# Zusatzprint_Raspberry_Pi_Zero.net
KiCad netlist of a schematic drawn in EAGLE
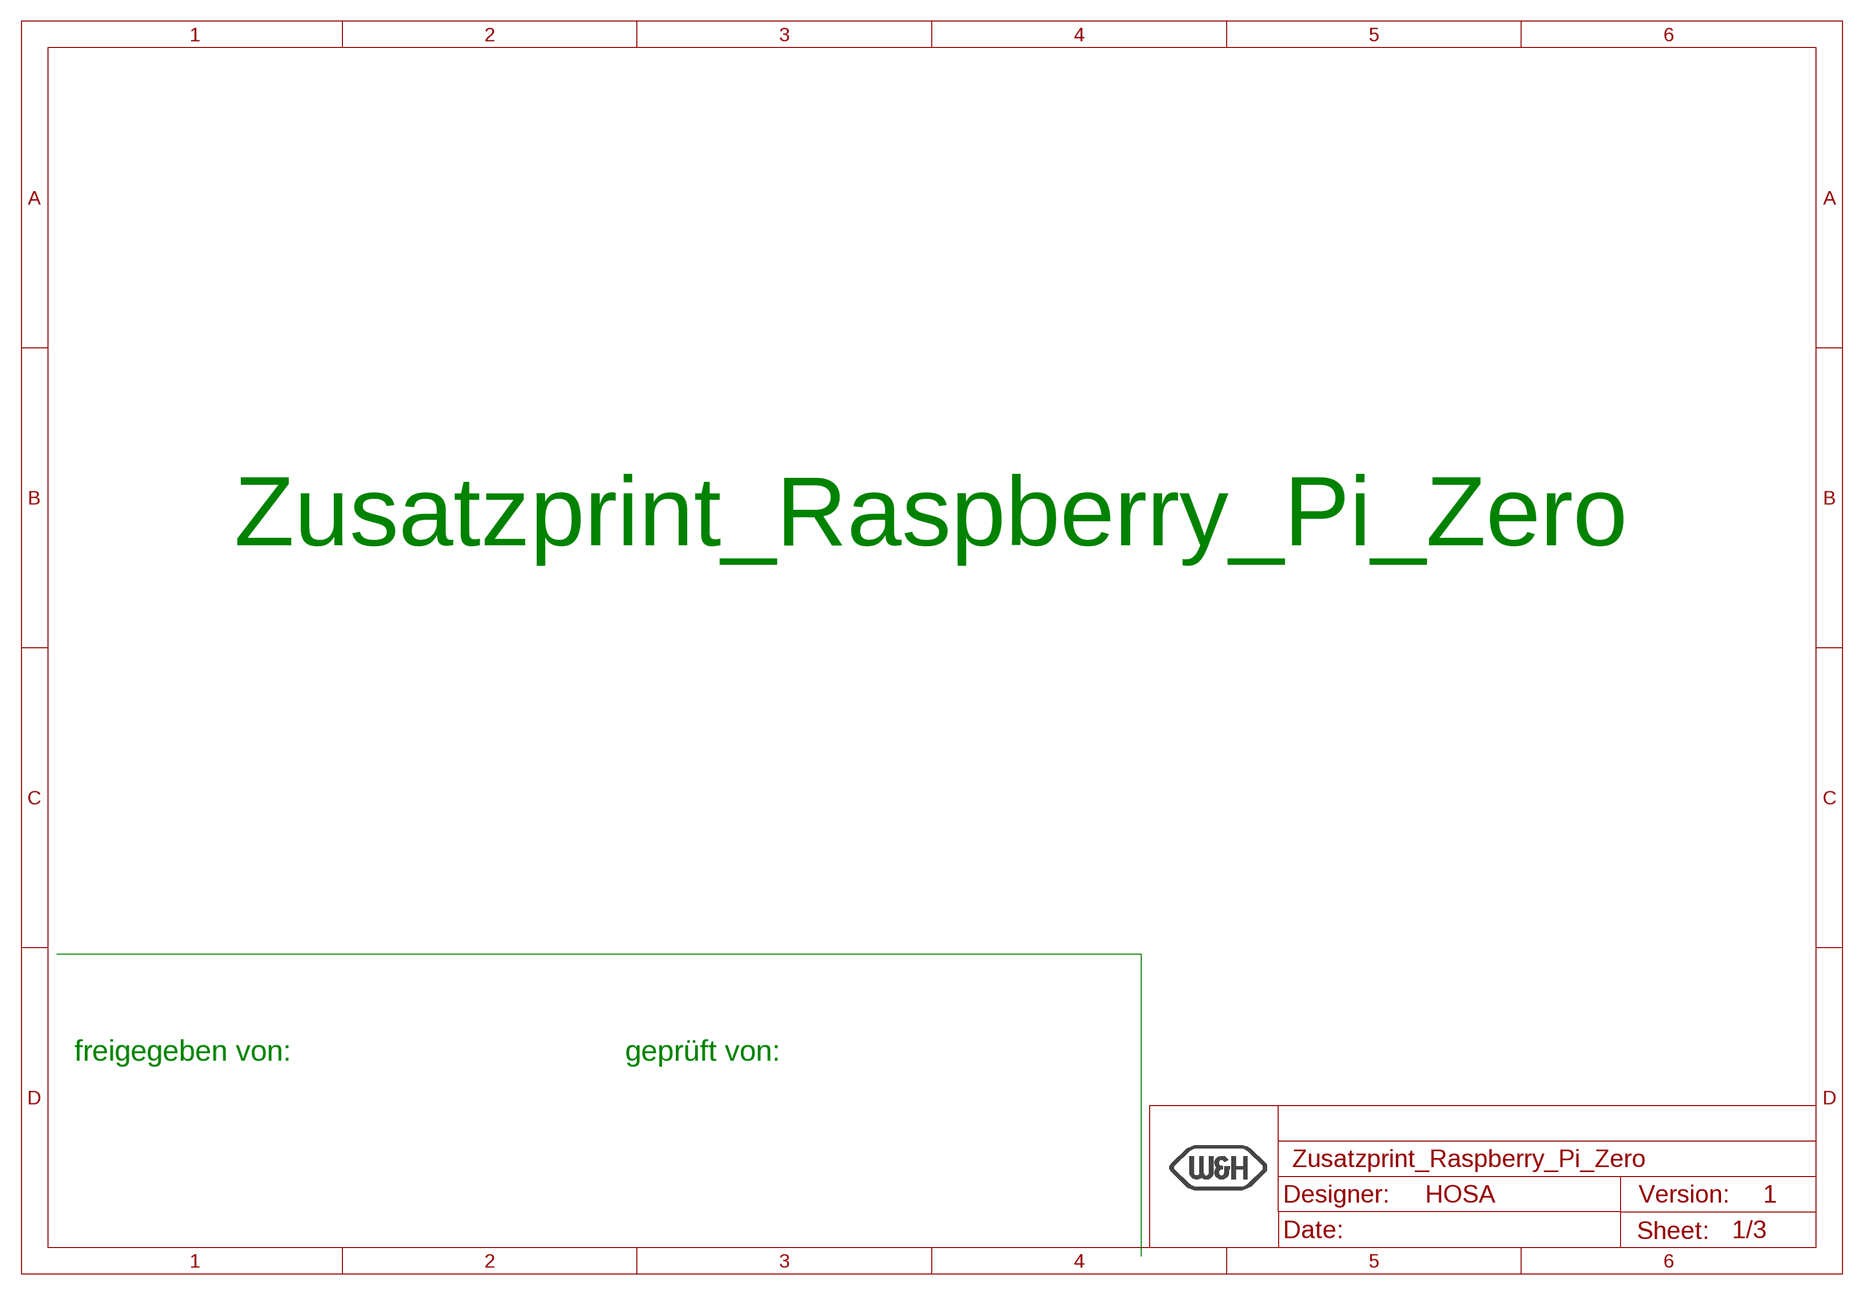
[diagram p0: schematic, sheet 1]
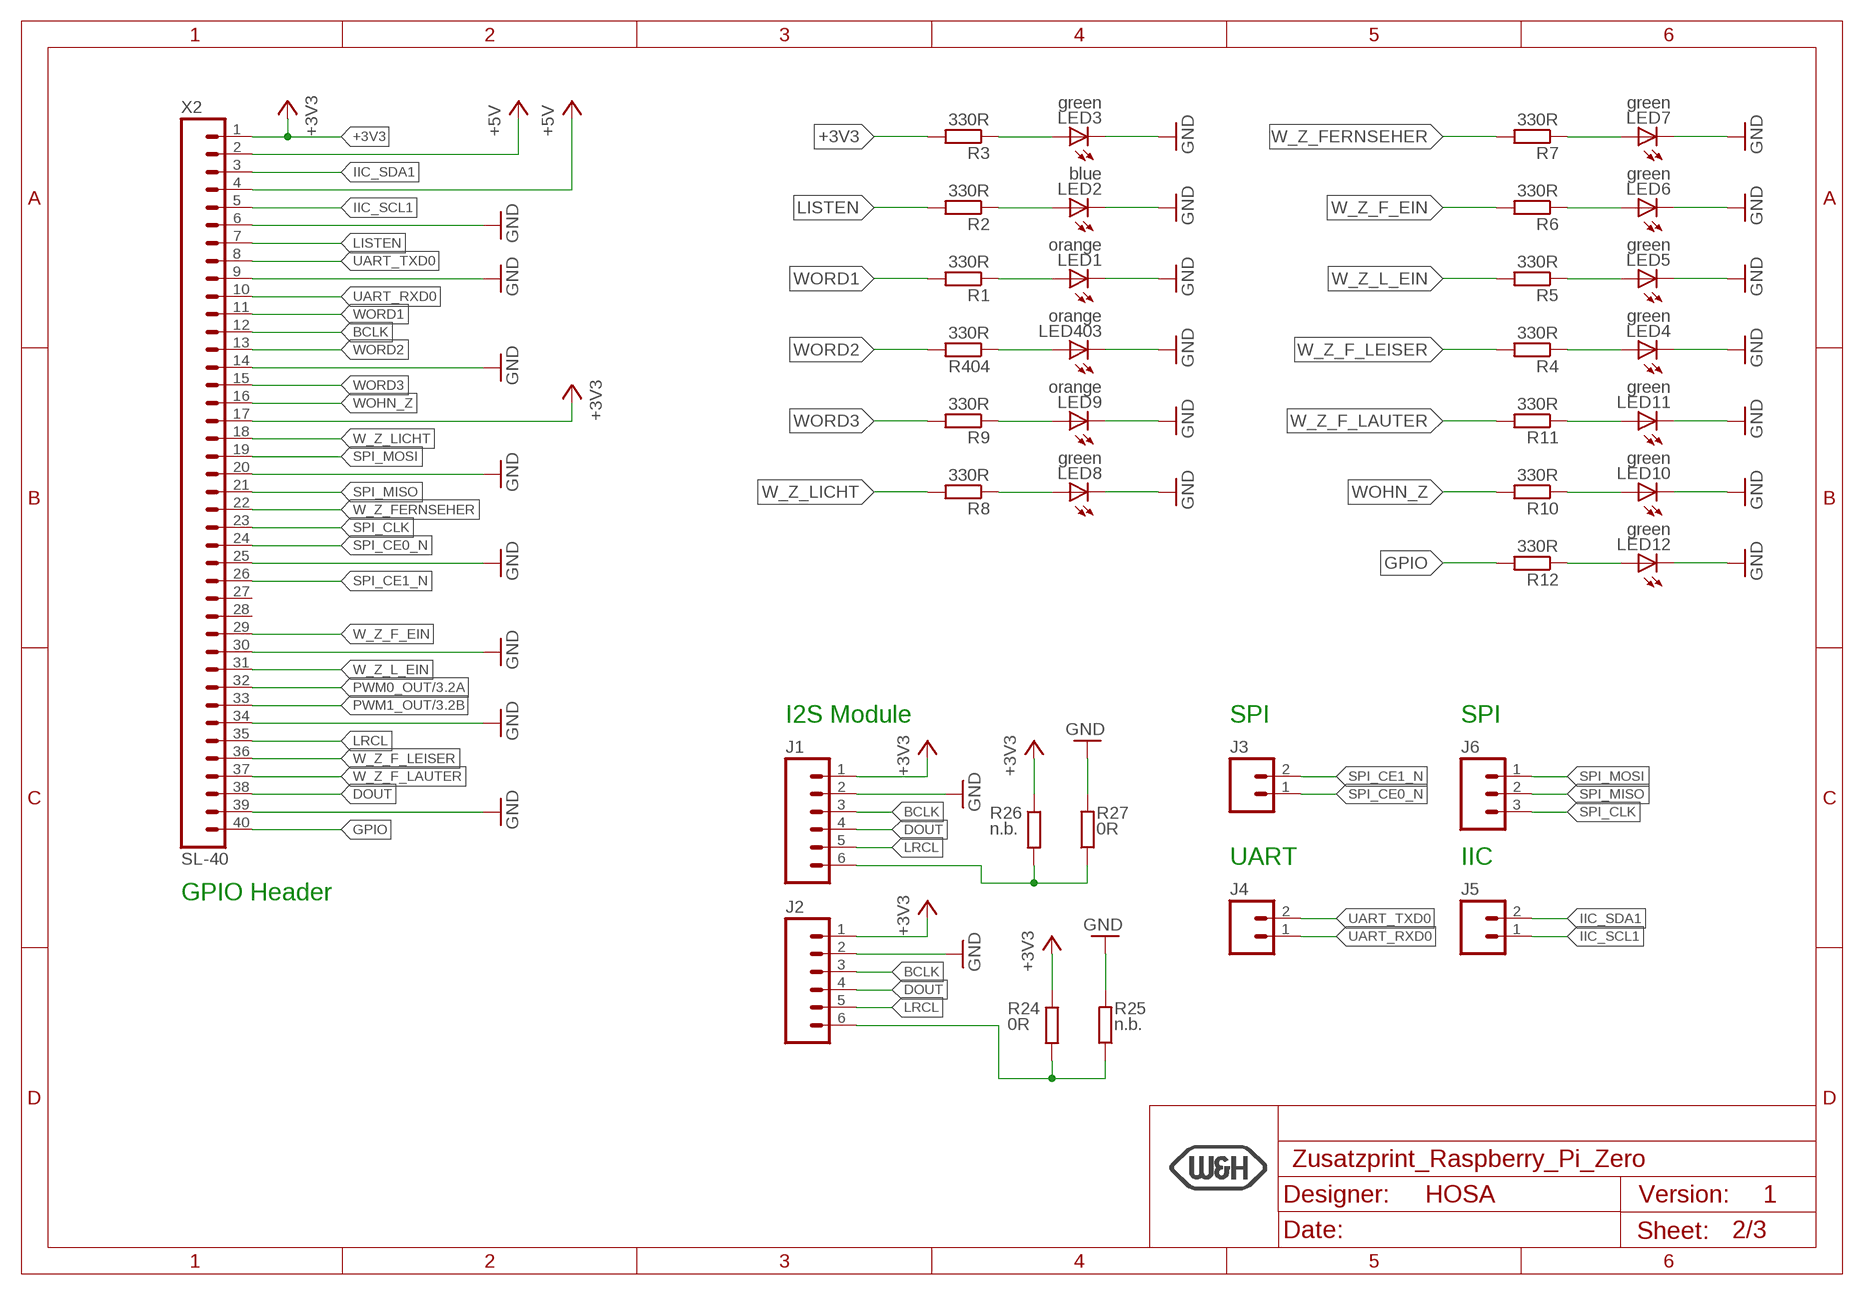
[diagram p1: schematic, sheet 2]
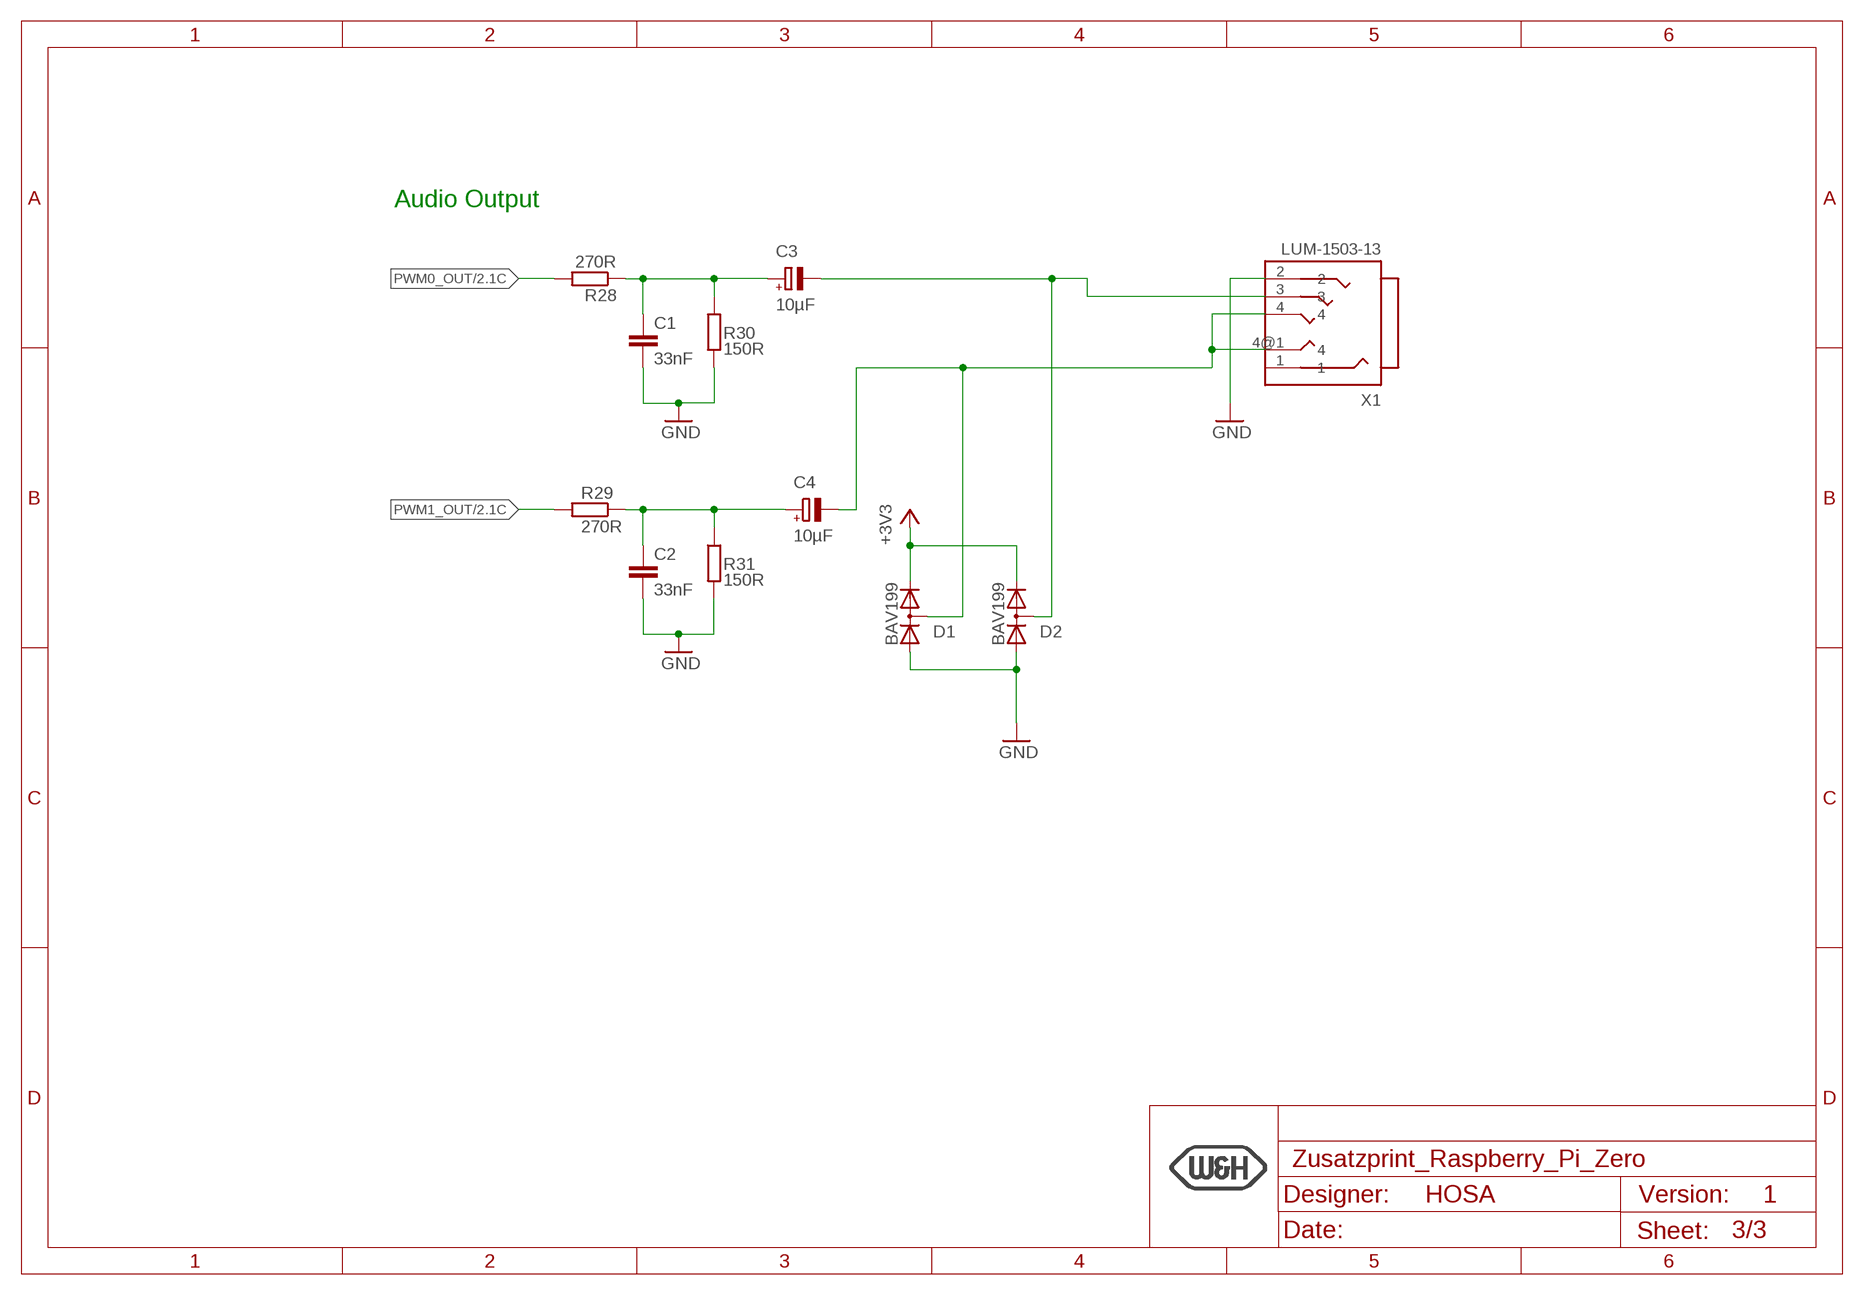
[diagram p2: schematic, sheet 3]

(export (version "E")
  (design (tool "Eeschema 10.0.6"))
  (components
    (comp (ref "J1")
      (value "S-LEISTE-06")
      (footprint "eagle-import:BL-06")
      (libsource (lib "eagle-import") (part "-LEISTE-06S"))
    )
    (comp (ref "J2")
      (value "S-LEISTE-06")
      (footprint "eagle-import:BL-06")
      (libsource (lib "eagle-import") (part "-LEISTE-06S"))
    )
    (comp (ref "J3")
      (value "S-LEISTE-02")
      (footprint "eagle-import:BL-02")
      (libsource (lib "eagle-import") (part "-LEISTE-02S"))
    )
    (comp (ref "J4")
      (value "S-LEISTE-02")
      (footprint "eagle-import:BL-02")
      (libsource (lib "eagle-import") (part "-LEISTE-02S"))
    )
    (comp (ref "J5")
      (value "S-LEISTE-02")
      (footprint "eagle-import:BL-02")
      (libsource (lib "eagle-import") (part "-LEISTE-02S"))
    )
    (comp (ref "J6")
      (value "S-LEISTE-03")
      (footprint "eagle-import:BL-03")
      (libsource (lib "eagle-import") (part "-LEISTE-03S"))
    )
    (comp (ref "LED1")
      (value "orange")
      (footprint "eagle-import:CHIP-LED0805")
      (libsource (lib "eagle-import") (part "LEDCHIP-LED0805"))
    )
    (comp (ref "LED2")
      (value "blue")
      (footprint "eagle-import:CHIP-LED0805")
      (libsource (lib "eagle-import") (part "LEDCHIP-LED0805"))
    )
    (comp (ref "LED3")
      (value "green")
      (footprint "eagle-import:CHIP-LED0805")
      (libsource (lib "eagle-import") (part "LEDCHIP-LED0805"))
    )
    (comp (ref "LED4")
      (value "green")
      (footprint "eagle-import:CHIP-LED0805")
      (libsource (lib "eagle-import") (part "LEDCHIP-LED0805"))
    )
    (comp (ref "LED5")
      (value "green")
      (footprint "eagle-import:CHIP-LED0805")
      (libsource (lib "eagle-import") (part "LEDCHIP-LED0805"))
    )
    (comp (ref "LED6")
      (value "green")
      (footprint "eagle-import:CHIP-LED0805")
      (libsource (lib "eagle-import") (part "LEDCHIP-LED0805"))
    )
    (comp (ref "LED7")
      (value "green")
      (footprint "eagle-import:CHIP-LED0805")
      (libsource (lib "eagle-import") (part "LEDCHIP-LED0805"))
    )
    (comp (ref "LED8")
      (value "green")
      (footprint "eagle-import:CHIP-LED0805")
      (libsource (lib "eagle-import") (part "LEDCHIP-LED0805"))
    )
    (comp (ref "LED9")
      (value "orange")
      (footprint "eagle-import:CHIP-LED0805")
      (libsource (lib "eagle-import") (part "LEDCHIP-LED0805"))
    )
    (comp (ref "LED10")
      (value "green")
      (footprint "eagle-import:CHIP-LED0805")
      (libsource (lib "eagle-import") (part "LEDCHIP-LED0805"))
    )
    (comp (ref "LED11")
      (value "green")
      (footprint "eagle-import:CHIP-LED0805")
      (libsource (lib "eagle-import") (part "LEDCHIP-LED0805"))
    )
    (comp (ref "LED12")
      (value "green")
      (footprint "eagle-import:CHIP-LED0805")
      (libsource (lib "eagle-import") (part "LEDCHIP-LED0805"))
    )
    (comp (ref "LED403")
      (value "orange")
      (footprint "eagle-import:CHIP-LED0805")
      (libsource (lib "eagle-import") (part "LEDCHIP-LED0805"))
    )
    (comp (ref "R1")
      (value "330R")
      (footprint "eagle-import:M0805")
      (libsource (lib "eagle-import") (part "R-EU_M0805"))
    )
    (comp (ref "R2")
      (value "330R")
      (footprint "eagle-import:M0805")
      (libsource (lib "eagle-import") (part "R-EU_M0805"))
    )
    (comp (ref "R3")
      (value "330R")
      (footprint "eagle-import:M0805")
      (libsource (lib "eagle-import") (part "R-EU_M0805"))
    )
    (comp (ref "R4")
      (value "330R")
      (footprint "eagle-import:M0805")
      (libsource (lib "eagle-import") (part "R-EU_M0805"))
    )
    (comp (ref "R5")
      (value "330R")
      (footprint "eagle-import:M0805")
      (libsource (lib "eagle-import") (part "R-EU_M0805"))
    )
    (comp (ref "R6")
      (value "330R")
      (footprint "eagle-import:M0805")
      (libsource (lib "eagle-import") (part "R-EU_M0805"))
    )
    (comp (ref "R7")
      (value "330R")
      (footprint "eagle-import:M0805")
      (libsource (lib "eagle-import") (part "R-EU_M0805"))
    )
    (comp (ref "R8")
      (value "330R")
      (footprint "eagle-import:M0805")
      (libsource (lib "eagle-import") (part "R-EU_M0805"))
    )
    (comp (ref "R9")
      (value "330R")
      (footprint "eagle-import:M0805")
      (libsource (lib "eagle-import") (part "R-EU_M0805"))
    )
    (comp (ref "R10")
      (value "330R")
      (footprint "eagle-import:M0805")
      (libsource (lib "eagle-import") (part "R-EU_M0805"))
    )
    (comp (ref "R11")
      (value "330R")
      (footprint "eagle-import:M0805")
      (libsource (lib "eagle-import") (part "R-EU_M0805"))
    )
    (comp (ref "R12")
      (value "330R")
      (footprint "eagle-import:M0805")
      (libsource (lib "eagle-import") (part "R-EU_M0805"))
    )
    (comp (ref "R24")
      (value "0R")
      (footprint "eagle-import:M0805")
      (libsource (lib "eagle-import") (part "R-EU_M0805"))
    )
    (comp (ref "R25")
      (value "n.b.")
      (footprint "eagle-import:M0805")
      (libsource (lib "eagle-import") (part "R-EU_M0805"))
    )
    (comp (ref "R26")
      (value "n.b.")
      (footprint "eagle-import:M0805")
      (libsource (lib "eagle-import") (part "R-EU_M0805"))
    )
    (comp (ref "R27")
      (value "0R")
      (footprint "eagle-import:M0805")
      (libsource (lib "eagle-import") (part "R-EU_M0805"))
    )
    (comp (ref "R404")
      (value "330R")
      (footprint "eagle-import:M0805")
      (libsource (lib "eagle-import") (part "R-EU_M0805"))
    )
    (comp (ref "X2")
      (value "SL-40")
      (footprint "eagle-import:SL_40")
      (libsource (lib "eagle-import") (part "SL-40"))
    )
    (comp (ref "C1")
      (value "33nF")
      (footprint "eagle-import:C0805")
      (libsource (lib "eagle-import") (part "C-EUC0805"))
    )
    (comp (ref "C2")
      (value "33nF")
      (footprint "eagle-import:C0805")
      (libsource (lib "eagle-import") (part "C-EUC0805"))
    )
    (comp (ref "C3")
      (value "10µF")
      (footprint "eagle-import:E2,5-6")
      (libsource (lib "eagle-import") (part "CPOL-EUE2.5-6"))
    )
    (comp (ref "C4")
      (value "10µF")
      (footprint "eagle-import:E2,5-6")
      (libsource (lib "eagle-import") (part "CPOL-EUE2.5-6"))
    )
    (comp (ref "D1")
      (value "BAV199")
      (footprint "eagle-import:SOT23")
      (libsource (lib "eagle-import") (part "BAV199"))
    )
    (comp (ref "D2")
      (value "BAV199")
      (footprint "eagle-import:SOT23")
      (libsource (lib "eagle-import") (part "BAV199"))
    )
    (comp (ref "R28")
      (value "270R")
      (footprint "eagle-import:M0805")
      (libsource (lib "eagle-import") (part "R-EU_M0805"))
    )
    (comp (ref "R29")
      (value "270R")
      (footprint "eagle-import:M0805")
      (libsource (lib "eagle-import") (part "R-EU_M0805"))
    )
    (comp (ref "R30")
      (value "150R")
      (footprint "eagle-import:M0805")
      (libsource (lib "eagle-import") (part "R-EU_M0805"))
    )
    (comp (ref "R31")
      (value "150R")
      (footprint "eagle-import:M0805")
      (libsource (lib "eagle-import") (part "R-EU_M0805"))
    )
    (comp (ref "X1")
      (value "LUM-1503-13")
      (footprint "eagle-import:1503-13")
      (fields (field (name "MF") "Lumberg") (field (name "MPN") "1503 13"))
      (libsource (lib "eagle-import") (part "LUM-1503-13"))
    )
  )
  (nets
    (net (code "1") (name "+3V3") (class "Default")
      (node (ref "D1") (pin "2") (pinfunction "C_2") (pintype "passive"))
      (node (ref "D2") (pin "2") (pinfunction "C_2") (pintype "passive"))
      (node (ref "J1") (pin "1") (pinfunction "1_1") (pintype "passive"))
      (node (ref "J2") (pin "1") (pinfunction "1_1") (pintype "passive"))
      (node (ref "R24") (pin "1") (pinfunction "1_1") (pintype "passive"))
      (node (ref "R26") (pin "1") (pinfunction "1_1") (pintype "passive"))
      (node (ref "R3") (pin "2") (pinfunction "2_2") (pintype "passive"))
      (node (ref "X2") (pin "1") (pinfunction "1_1") (pintype "passive"))
      (node (ref "X2") (pin "17") (pinfunction "17_17") (pintype "passive"))
    )
    (net (code "2") (name "+5V") (class "Default")
      (node (ref "X2") (pin "2") (pinfunction "2_2") (pintype "passive"))
      (node (ref "X2") (pin "4") (pinfunction "4_4") (pintype "passive"))
    )
    (net (code "3") (name "BCLK") (class "Default")
      (node (ref "J1") (pin "3") (pinfunction "3_3") (pintype "passive"))
      (node (ref "J2") (pin "3") (pinfunction "3_3") (pintype "passive"))
      (node (ref "X2") (pin "12") (pinfunction "12_12") (pintype "passive"))
    )
    (net (code "4") (name "DOUT") (class "Default")
      (node (ref "J1") (pin "4") (pinfunction "4_4") (pintype "passive"))
      (node (ref "J2") (pin "4") (pinfunction "4_4") (pintype "passive"))
      (node (ref "X2") (pin "38") (pinfunction "38_38") (pintype "passive"))
    )
    (net (code "5") (name "GND") (class "Default")
      (node (ref "C1") (pin "2") (pinfunction "2_2") (pintype "passive"))
      (node (ref "C2") (pin "2") (pinfunction "2_2") (pintype "passive"))
      (node (ref "D1") (pin "1") (pinfunction "A_1") (pintype "passive"))
      (node (ref "D2") (pin "1") (pinfunction "A_1") (pintype "passive"))
      (node (ref "J1") (pin "2") (pinfunction "2_2") (pintype "passive"))
      (node (ref "J2") (pin "2") (pinfunction "2_2") (pintype "passive"))
      (node (ref "LED1") (pin "C") (pinfunction "C_C") (pintype "passive"))
      (node (ref "LED10") (pin "C") (pinfunction "C_C") (pintype "passive"))
      (node (ref "LED11") (pin "C") (pinfunction "C_C") (pintype "passive"))
      (node (ref "LED12") (pin "C") (pinfunction "C_C") (pintype "passive"))
      (node (ref "LED2") (pin "C") (pinfunction "C_C") (pintype "passive"))
      (node (ref "LED3") (pin "C") (pinfunction "C_C") (pintype "passive"))
      (node (ref "LED4") (pin "C") (pinfunction "C_C") (pintype "passive"))
      (node (ref "LED403") (pin "C") (pinfunction "C_C") (pintype "passive"))
      (node (ref "LED5") (pin "C") (pinfunction "C_C") (pintype "passive"))
      (node (ref "LED6") (pin "C") (pinfunction "C_C") (pintype "passive"))
      (node (ref "LED7") (pin "C") (pinfunction "C_C") (pintype "passive"))
      (node (ref "LED8") (pin "C") (pinfunction "C_C") (pintype "passive"))
      (node (ref "LED9") (pin "C") (pinfunction "C_C") (pintype "passive"))
      (node (ref "R25") (pin "2") (pinfunction "2_2") (pintype "passive"))
      (node (ref "R27") (pin "2") (pinfunction "2_2") (pintype "passive"))
      (node (ref "R30") (pin "2") (pinfunction "2_2") (pintype "passive"))
      (node (ref "R31") (pin "2") (pinfunction "2_2") (pintype "passive"))
      (node (ref "X1") (pin "2") (pinfunction "2_2") (pintype "bidirectional"))
      (node (ref "X2") (pin "14") (pinfunction "14_14") (pintype "passive"))
      (node (ref "X2") (pin "20") (pinfunction "20_20") (pintype "passive"))
      (node (ref "X2") (pin "25") (pinfunction "25_25") (pintype "passive"))
      (node (ref "X2") (pin "30") (pinfunction "30_30") (pintype "passive"))
      (node (ref "X2") (pin "34") (pinfunction "34_34") (pintype "passive"))
      (node (ref "X2") (pin "39") (pinfunction "39_39") (pintype "passive"))
      (node (ref "X2") (pin "6") (pinfunction "6_6") (pintype "passive"))
      (node (ref "X2") (pin "9") (pinfunction "9_9") (pintype "passive"))
    )
    (net (code "6") (name "GPIO") (class "Default")
      (node (ref "R12") (pin "2") (pinfunction "2_2") (pintype "passive"))
      (node (ref "X2") (pin "40") (pinfunction "40_40") (pintype "passive"))
    )
    (net (code "7") (name "IIC_SCL1") (class "Default")
      (node (ref "J5") (pin "1") (pinfunction "1_1") (pintype "passive"))
      (node (ref "X2") (pin "5") (pinfunction "5_5") (pintype "passive"))
    )
    (net (code "8") (name "IIC_SDA1") (class "Default")
      (node (ref "J5") (pin "2") (pinfunction "2_2") (pintype "passive"))
      (node (ref "X2") (pin "3") (pinfunction "3_3") (pintype "passive"))
    )
    (net (code "9") (name "LISTEN") (class "Default")
      (node (ref "R2") (pin "2") (pinfunction "2_2") (pintype "passive"))
      (node (ref "X2") (pin "7") (pinfunction "7_7") (pintype "passive"))
    )
    (net (code "10") (name "LRCL") (class "Default")
      (node (ref "J1") (pin "5") (pinfunction "5_5") (pintype "passive"))
      (node (ref "J2") (pin "5") (pinfunction "5_5") (pintype "passive"))
      (node (ref "X2") (pin "35") (pinfunction "35_35") (pintype "passive"))
    )
    (net (code "11") (name "Net-(C1-Pad1)") (class "Default")
      (node (ref "C1") (pin "1") (pinfunction "1_1") (pintype "passive"))
      (node (ref "C3") (pin "+") (pinfunction "+_+") (pintype "passive"))
      (node (ref "R28") (pin "1") (pinfunction "1_1") (pintype "passive"))
      (node (ref "R30") (pin "1") (pinfunction "1_1") (pintype "passive"))
    )
    (net (code "12") (name "Net-(C2-Pad1)") (class "Default")
      (node (ref "C2") (pin "1") (pinfunction "1_1") (pintype "passive"))
      (node (ref "C4") (pin "+") (pinfunction "+_+") (pintype "passive"))
      (node (ref "R29") (pin "1") (pinfunction "1_1") (pintype "passive"))
      (node (ref "R31") (pin "1") (pinfunction "1_1") (pintype "passive"))
    )
    (net (code "13") (name "Net-(D1-AC)") (class "Default")
      (node (ref "C4") (pin "-") (pinfunction "-_-") (pintype "passive"))
      (node (ref "D1") (pin "3") (pinfunction "AC_3") (pintype "passive"))
      (node (ref "X1") (pin "4") (pinfunction "4_4") (pintype "bidirectional"))
      (node (ref "X1") (pin "4@1") (pinfunction "4_4@1") (pintype "bidirectional"))
    )
    (net (code "14") (name "Net-(D2-AC)") (class "Default")
      (node (ref "C3") (pin "-") (pinfunction "-_-") (pintype "passive"))
      (node (ref "D2") (pin "3") (pinfunction "AC_3") (pintype "passive"))
      (node (ref "X1") (pin "3") (pinfunction "3_3") (pintype "bidirectional"))
    )
    (net (code "15") (name "Net-(J1-Pad6)") (class "Default")
      (node (ref "J1") (pin "6") (pinfunction "6_6") (pintype "passive"))
      (node (ref "R26") (pin "2") (pinfunction "2_2") (pintype "passive"))
      (node (ref "R27") (pin "1") (pinfunction "1_1") (pintype "passive"))
    )
    (net (code "16") (name "Net-(J2-Pad6)") (class "Default")
      (node (ref "J2") (pin "6") (pinfunction "6_6") (pintype "passive"))
      (node (ref "R24") (pin "2") (pinfunction "2_2") (pintype "passive"))
      (node (ref "R25") (pin "1") (pinfunction "1_1") (pintype "passive"))
    )
    (net (code "17") (name "Net-(LED1-PadA)") (class "Default")
      (node (ref "LED1") (pin "A") (pinfunction "A_A") (pintype "passive"))
      (node (ref "R1") (pin "1") (pinfunction "1_1") (pintype "passive"))
    )
    (net (code "18") (name "Net-(LED2-PadA)") (class "Default")
      (node (ref "LED2") (pin "A") (pinfunction "A_A") (pintype "passive"))
      (node (ref "R2") (pin "1") (pinfunction "1_1") (pintype "passive"))
    )
    (net (code "19") (name "Net-(LED3-PadA)") (class "Default")
      (node (ref "LED3") (pin "A") (pinfunction "A_A") (pintype "passive"))
      (node (ref "R3") (pin "1") (pinfunction "1_1") (pintype "passive"))
    )
    (net (code "20") (name "Net-(LED4-PadA)") (class "Default")
      (node (ref "LED4") (pin "A") (pinfunction "A_A") (pintype "passive"))
      (node (ref "R4") (pin "1") (pinfunction "1_1") (pintype "passive"))
    )
    (net (code "21") (name "Net-(LED5-PadA)") (class "Default")
      (node (ref "LED5") (pin "A") (pinfunction "A_A") (pintype "passive"))
      (node (ref "R5") (pin "1") (pinfunction "1_1") (pintype "passive"))
    )
    (net (code "22") (name "Net-(LED6-PadA)") (class "Default")
      (node (ref "LED6") (pin "A") (pinfunction "A_A") (pintype "passive"))
      (node (ref "R6") (pin "1") (pinfunction "1_1") (pintype "passive"))
    )
    (net (code "23") (name "Net-(LED7-PadA)") (class "Default")
      (node (ref "LED7") (pin "A") (pinfunction "A_A") (pintype "passive"))
      (node (ref "R7") (pin "1") (pinfunction "1_1") (pintype "passive"))
    )
    (net (code "24") (name "Net-(LED8-PadA)") (class "Default")
      (node (ref "LED8") (pin "A") (pinfunction "A_A") (pintype "passive"))
      (node (ref "R8") (pin "1") (pinfunction "1_1") (pintype "passive"))
    )
    (net (code "25") (name "Net-(LED9-PadA)") (class "Default")
      (node (ref "LED9") (pin "A") (pinfunction "A_A") (pintype "passive"))
      (node (ref "R9") (pin "1") (pinfunction "1_1") (pintype "passive"))
    )
    (net (code "26") (name "Net-(LED10-PadA)") (class "Default")
      (node (ref "LED10") (pin "A") (pinfunction "A_A") (pintype "passive"))
      (node (ref "R10") (pin "1") (pinfunction "1_1") (pintype "passive"))
    )
    (net (code "27") (name "Net-(LED11-PadA)") (class "Default")
      (node (ref "LED11") (pin "A") (pinfunction "A_A") (pintype "passive"))
      (node (ref "R11") (pin "1") (pinfunction "1_1") (pintype "passive"))
    )
    (net (code "28") (name "Net-(LED12-PadA)") (class "Default")
      (node (ref "LED12") (pin "A") (pinfunction "A_A") (pintype "passive"))
      (node (ref "R12") (pin "1") (pinfunction "1_1") (pintype "passive"))
    )
    (net (code "29") (name "Net-(LED403-PadA)") (class "Default")
      (node (ref "LED403") (pin "A") (pinfunction "A_A") (pintype "passive"))
      (node (ref "R404") (pin "1") (pinfunction "1_1") (pintype "passive"))
    )
    (net (code "30") (name "PWM0_OUT") (class "Default")
      (node (ref "R28") (pin "2") (pinfunction "2_2") (pintype "passive"))
      (node (ref "X2") (pin "32") (pinfunction "32_32") (pintype "passive"))
    )
    (net (code "31") (name "PWM1_OUT") (class "Default")
      (node (ref "R29") (pin "2") (pinfunction "2_2") (pintype "passive"))
      (node (ref "X2") (pin "33") (pinfunction "33_33") (pintype "passive"))
    )
    (net (code "32") (name "SPI_CE0_N") (class "Default")
      (node (ref "J3") (pin "1") (pinfunction "1_1") (pintype "passive"))
      (node (ref "X2") (pin "24") (pinfunction "24_24") (pintype "passive"))
    )
    (net (code "33") (name "SPI_CE1_N") (class "Default")
      (node (ref "J3") (pin "2") (pinfunction "2_2") (pintype "passive"))
      (node (ref "X2") (pin "26") (pinfunction "26_26") (pintype "passive"))
    )
    (net (code "34") (name "SPI_CLK") (class "Default")
      (node (ref "J6") (pin "3") (pinfunction "3_3") (pintype "passive"))
      (node (ref "X2") (pin "23") (pinfunction "23_23") (pintype "passive"))
    )
    (net (code "35") (name "SPI_MISO") (class "Default")
      (node (ref "J6") (pin "2") (pinfunction "2_2") (pintype "passive"))
      (node (ref "X2") (pin "21") (pinfunction "21_21") (pintype "passive"))
    )
    (net (code "36") (name "SPI_MOSI") (class "Default")
      (node (ref "J6") (pin "1") (pinfunction "1_1") (pintype "passive"))
      (node (ref "X2") (pin "19") (pinfunction "19_19") (pintype "passive"))
    )
    (net (code "37") (name "UART_RXD0") (class "Default")
      (node (ref "J4") (pin "1") (pinfunction "1_1") (pintype "passive"))
      (node (ref "X2") (pin "10") (pinfunction "10_10") (pintype "passive"))
    )
    (net (code "38") (name "UART_TXD0") (class "Default")
      (node (ref "J4") (pin "2") (pinfunction "2_2") (pintype "passive"))
      (node (ref "X2") (pin "8") (pinfunction "8_8") (pintype "passive"))
    )
    (net (code "39") (name "WOHN_Z") (class "Default")
      (node (ref "R10") (pin "2") (pinfunction "2_2") (pintype "passive"))
      (node (ref "X2") (pin "16") (pinfunction "16_16") (pintype "passive"))
    )
    (net (code "40") (name "WORD1") (class "Default")
      (node (ref "R1") (pin "2") (pinfunction "2_2") (pintype "passive"))
      (node (ref "X2") (pin "11") (pinfunction "11_11") (pintype "passive"))
    )
    (net (code "41") (name "WORD2") (class "Default")
      (node (ref "R404") (pin "2") (pinfunction "2_2") (pintype "passive"))
      (node (ref "X2") (pin "13") (pinfunction "13_13") (pintype "passive"))
    )
    (net (code "42") (name "WORD3") (class "Default")
      (node (ref "R9") (pin "2") (pinfunction "2_2") (pintype "passive"))
      (node (ref "X2") (pin "15") (pinfunction "15_15") (pintype "passive"))
    )
    (net (code "43") (name "W_Z_FERNSEHER") (class "Default")
      (node (ref "R7") (pin "2") (pinfunction "2_2") (pintype "passive"))
      (node (ref "X2") (pin "22") (pinfunction "22_22") (pintype "passive"))
    )
    (net (code "44") (name "W_Z_F_EIN") (class "Default")
      (node (ref "R6") (pin "2") (pinfunction "2_2") (pintype "passive"))
      (node (ref "X2") (pin "29") (pinfunction "29_29") (pintype "passive"))
    )
    (net (code "45") (name "W_Z_F_LAUTER") (class "Default")
      (node (ref "R11") (pin "2") (pinfunction "2_2") (pintype "passive"))
      (node (ref "X2") (pin "37") (pinfunction "37_37") (pintype "passive"))
    )
    (net (code "46") (name "W_Z_F_LEISER") (class "Default")
      (node (ref "R4") (pin "2") (pinfunction "2_2") (pintype "passive"))
      (node (ref "X2") (pin "36") (pinfunction "36_36") (pintype "passive"))
    )
    (net (code "47") (name "W_Z_LICHT") (class "Default")
      (node (ref "R8") (pin "2") (pinfunction "2_2") (pintype "passive"))
      (node (ref "X2") (pin "18") (pinfunction "18_18") (pintype "passive"))
    )
    (net (code "48") (name "W_Z_L_EIN") (class "Default")
      (node (ref "R5") (pin "2") (pinfunction "2_2") (pintype "passive"))
      (node (ref "X2") (pin "31") (pinfunction "31_31") (pintype "passive"))
    )
    (net (code "49") (name "unconnected-(X1-Pad1)") (class "Default")
      (node (ref "X1") (pin "1") (pinfunction "1_1") (pintype "bidirectional"))
    )
    (net (code "50") (name "unconnected-(X2-Pad27)") (class "Default")
      (node (ref "X2") (pin "27") (pinfunction "27_27") (pintype "passive"))
    )
    (net (code "51") (name "unconnected-(X2-Pad28)") (class "Default")
      (node (ref "X2") (pin "28") (pinfunction "28_28") (pintype "passive"))
    )
  )
)
